# Hb_Wireless_TWELITE_2main.net
KiCad netlist of a schematic drawn in EAGLE
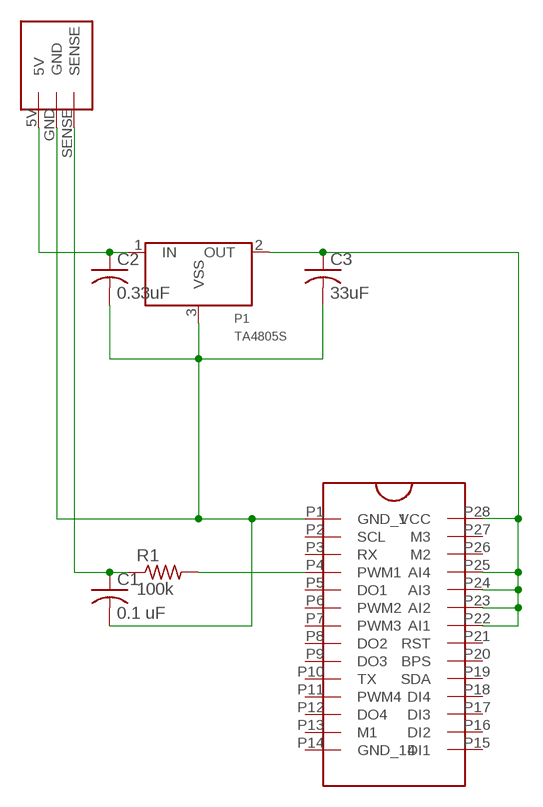
[diagram p0: schematic, sheet 1]

(export (version "E")
  (design (tool "Eeschema 10.0.6"))
  (components
    (comp (ref "C1")
      (value "0.1 uF")
      (footprint "eagle-import:C050-024X044")
      (libsource (lib "eagle-import") (part "C-US050-024X044"))
    )
    (comp (ref "C2")
      (value "0.33uF")
      (footprint "eagle-import:C050-024X044")
      (libsource (lib "eagle-import") (part "C-US050-024X044"))
    )
    (comp (ref "C3")
      (value "33uF")
      (footprint "eagle-import:C050-024X044")
      (libsource (lib "eagle-import") (part "C-US050-024X044"))
    )
    (comp (ref "P1")
      (value "TA4805S")
      (footprint "eagle-import:TA48__S")
      (libsource (lib "eagle-import") (part "TA4805S"))
    )
    (comp (ref "R1")
      (value "100k")
      (footprint "eagle-import:0207_7")
      (libsource (lib "eagle-import") (part "R-US_0207/7"))
    )
    (comp (ref "U$1")
      (value "TWE-LITE-DIP")
      (footprint "eagle-import:TWE-LITE-DIP")
      (libsource (lib "eagle-import") (part "TWE-LITE-DIP"))
    )
    (comp (ref "U$2")
      (value "CON2MAIN")
      (footprint "eagle-import:CON2MAIN")
      (libsource (lib "eagle-import") (part "CON2MAIN"))
    )
  )
  (nets
    (net (code "1") (name "Net-(C1-Pad1)") (class "Default")
      (node (ref "C1") (pin "1") (pinfunction "1_1") (pintype "passive"))
      (node (ref "R1") (pin "1") (pinfunction "1_1") (pintype "passive"))
      (node (ref "U$2") (pin "SENSE") (pinfunction "SENSE_SENSE") (pintype "bidirectional"))
    )
    (net (code "2") (name "Net-(P1-IN)") (class "Default")
      (node (ref "C2") (pin "1") (pinfunction "1_1") (pintype "passive"))
      (node (ref "P1") (pin "1") (pinfunction "IN_1") (pintype "bidirectional"))
      (node (ref "U$2") (pin "5V") (pinfunction "5V_5V") (pintype "bidirectional"))
    )
    (net (code "3") (name "Net-(P1-OUT)") (class "Default")
      (node (ref "C3") (pin "1") (pinfunction "1_1") (pintype "passive"))
      (node (ref "P1") (pin "2") (pinfunction "OUT_2") (pintype "bidirectional"))
      (node (ref "U$1") (pin "P22") (pinfunction "AI1_P22") (pintype "bidirectional"))
      (node (ref "U$1") (pin "P23") (pinfunction "AI2_P23") (pintype "bidirectional"))
      (node (ref "U$1") (pin "P24") (pinfunction "AI3_P24") (pintype "bidirectional"))
      (node (ref "U$1") (pin "P25") (pinfunction "AI4_P25") (pintype "bidirectional"))
      (node (ref "U$1") (pin "P28") (pinfunction "VCC_P28") (pintype "bidirectional"))
    )
    (net (code "4") (name "Net-(P1-VSS)") (class "Default")
      (node (ref "C1") (pin "2") (pinfunction "2_2") (pintype "passive"))
      (node (ref "C2") (pin "2") (pinfunction "2_2") (pintype "passive"))
      (node (ref "C3") (pin "2") (pinfunction "2_2") (pintype "passive"))
      (node (ref "P1") (pin "3") (pinfunction "VSS_3") (pintype "bidirectional"))
      (node (ref "U$1") (pin "P1") (pinfunction "GND_1_P1") (pintype "bidirectional"))
      (node (ref "U$2") (pin "GND") (pinfunction "GND_GND") (pintype "bidirectional"))
    )
    (net (code "5") (name "Net-(U$1-PWM1)") (class "Default")
      (node (ref "R1") (pin "2") (pinfunction "2_2") (pintype "passive"))
      (node (ref "U$1") (pin "P4") (pinfunction "PWM1_P4") (pintype "bidirectional"))
    )
    (net (code "6") (name "unconnected-(U$1-BPS-PadP20)") (class "Default")
      (node (ref "U$1") (pin "P20") (pinfunction "BPS_P20") (pintype "bidirectional"))
    )
    (net (code "7") (name "unconnected-(U$1-DI1-PadP15)") (class "Default")
      (node (ref "U$1") (pin "P15") (pinfunction "DI1_P15") (pintype "bidirectional"))
    )
    (net (code "8") (name "unconnected-(U$1-DI2-PadP16)") (class "Default")
      (node (ref "U$1") (pin "P16") (pinfunction "DI2_P16") (pintype "bidirectional"))
    )
    (net (code "9") (name "unconnected-(U$1-DI3-PadP17)") (class "Default")
      (node (ref "U$1") (pin "P17") (pinfunction "DI3_P17") (pintype "bidirectional"))
    )
    (net (code "10") (name "unconnected-(U$1-DI4-PadP18)") (class "Default")
      (node (ref "U$1") (pin "P18") (pinfunction "DI4_P18") (pintype "bidirectional"))
    )
    (net (code "11") (name "unconnected-(U$1-DO1-PadP5)") (class "Default")
      (node (ref "U$1") (pin "P5") (pinfunction "DO1_P5") (pintype "bidirectional"))
    )
    (net (code "12") (name "unconnected-(U$1-DO2-PadP8)") (class "Default")
      (node (ref "U$1") (pin "P8") (pinfunction "DO2_P8") (pintype "bidirectional"))
    )
    (net (code "13") (name "unconnected-(U$1-DO3-PadP9)") (class "Default")
      (node (ref "U$1") (pin "P9") (pinfunction "DO3_P9") (pintype "bidirectional"))
    )
    (net (code "14") (name "unconnected-(U$1-DO4-PadP12)") (class "Default")
      (node (ref "U$1") (pin "P12") (pinfunction "DO4_P12") (pintype "bidirectional"))
    )
    (net (code "15") (name "unconnected-(U$1-GND_14-PadP14)") (class "Default")
      (node (ref "U$1") (pin "P14") (pinfunction "GND_14_P14") (pintype "bidirectional"))
    )
    (net (code "16") (name "unconnected-(U$1-M1-PadP13)") (class "Default")
      (node (ref "U$1") (pin "P13") (pinfunction "M1_P13") (pintype "bidirectional"))
    )
    (net (code "17") (name "unconnected-(U$1-M2-PadP26)") (class "Default")
      (node (ref "U$1") (pin "P26") (pinfunction "M2_P26") (pintype "bidirectional"))
    )
    (net (code "18") (name "unconnected-(U$1-M3-PadP27)") (class "Default")
      (node (ref "U$1") (pin "P27") (pinfunction "M3_P27") (pintype "bidirectional"))
    )
    (net (code "19") (name "unconnected-(U$1-PWM2-PadP6)") (class "Default")
      (node (ref "U$1") (pin "P6") (pinfunction "PWM2_P6") (pintype "bidirectional"))
    )
    (net (code "20") (name "unconnected-(U$1-PWM3-PadP7)") (class "Default")
      (node (ref "U$1") (pin "P7") (pinfunction "PWM3_P7") (pintype "bidirectional"))
    )
    (net (code "21") (name "unconnected-(U$1-PWM4-PadP11)") (class "Default")
      (node (ref "U$1") (pin "P11") (pinfunction "PWM4_P11") (pintype "bidirectional"))
    )
    (net (code "22") (name "unconnected-(U$1-RST-PadP21)") (class "Default")
      (node (ref "U$1") (pin "P21") (pinfunction "RST_P21") (pintype "bidirectional"))
    )
    (net (code "23") (name "unconnected-(U$1-RX-PadP3)") (class "Default")
      (node (ref "U$1") (pin "P3") (pinfunction "RX_P3") (pintype "bidirectional"))
    )
    (net (code "24") (name "unconnected-(U$1-SCL-PadP2)") (class "Default")
      (node (ref "U$1") (pin "P2") (pinfunction "SCL_P2") (pintype "bidirectional"))
    )
    (net (code "25") (name "unconnected-(U$1-SDA-PadP19)") (class "Default")
      (node (ref "U$1") (pin "P19") (pinfunction "SDA_P19") (pintype "bidirectional"))
    )
    (net (code "26") (name "unconnected-(U$1-TX-PadP10)") (class "Default")
      (node (ref "U$1") (pin "P10") (pinfunction "TX_P10") (pintype "bidirectional"))
    )
  )
)
